# ShiftMux.net
KiCad netlist of a schematic drawn in Altium Designer
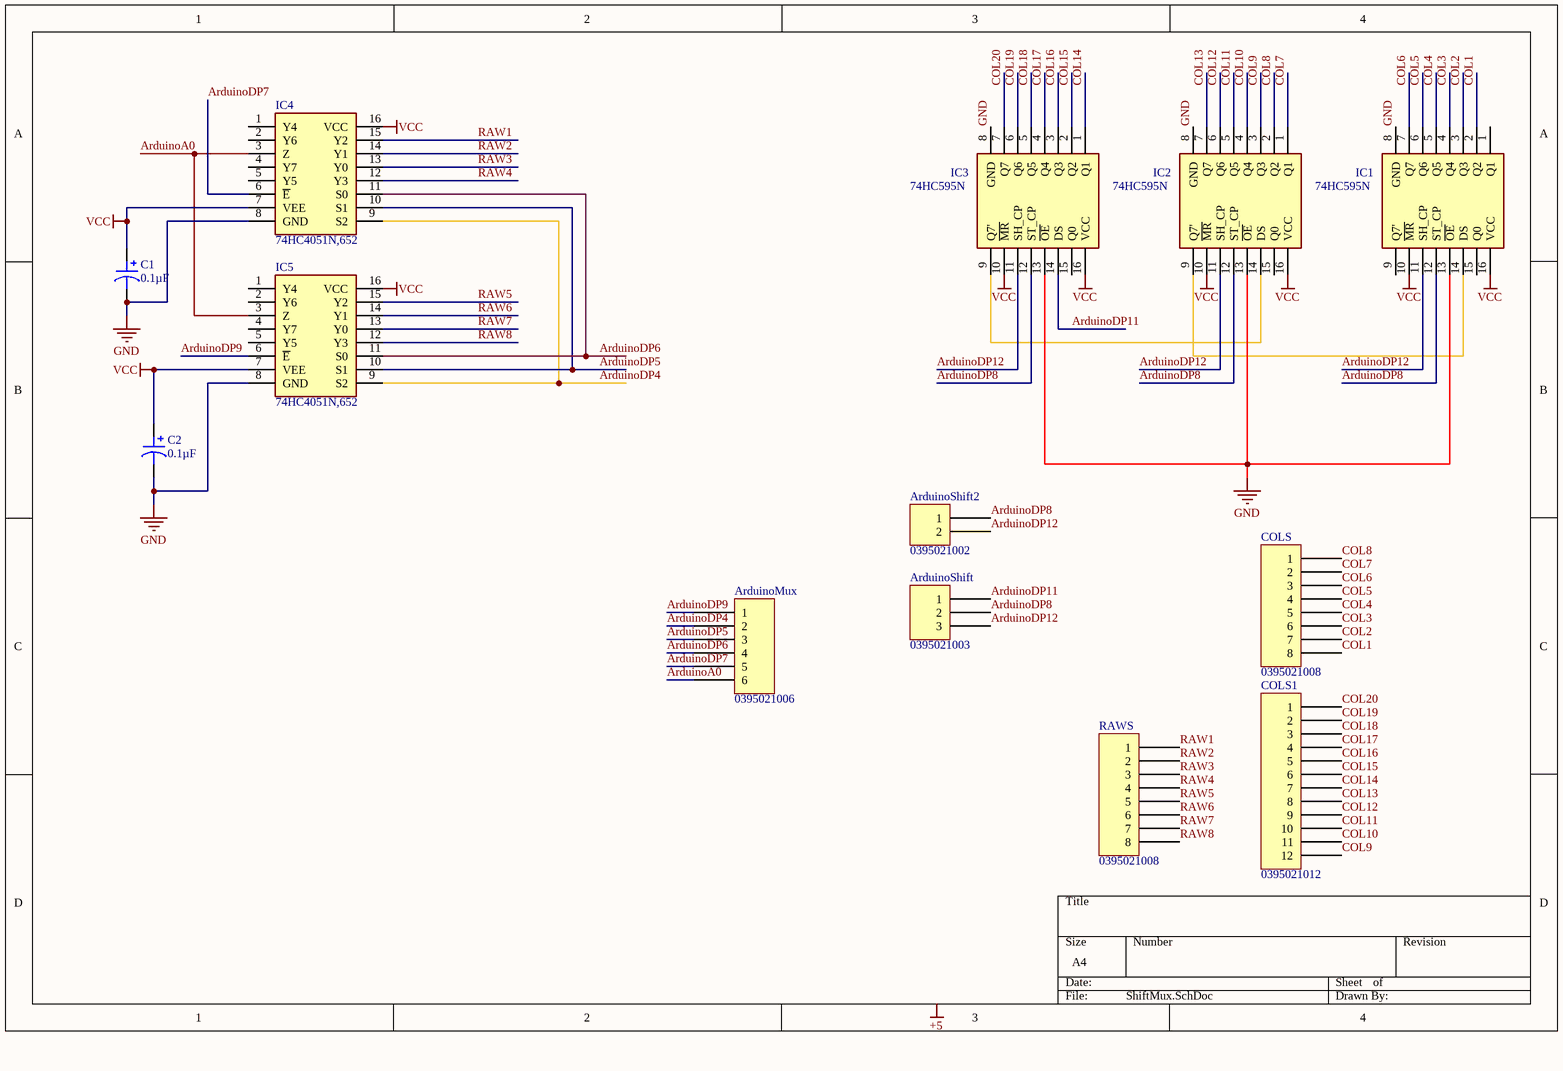
[diagram p0: ShiftMux.SchDoc]

(export (version "E")
  (design (tool "Eeschema 10.0.6"))
  (components
    (comp (ref "ArduinoMux")
      (value "0395021006")
      (footprint "MOLEX 395021006")
      (description "TERM BLOCK HDR 6POS 90DEG 3.5MM")
      (fields (field (name "MANUFACTURER") "Molex"))
      (libsource (lib "Celestial Altium Library - altium_library") (part "6 Pin"))
    )
    (comp (ref "ArduinoShift")
      (value "0395021003")
      (footprint "MOLEX 395021003")
      (description "TERM BLOCK HDR 3POS 90DEG 3.5MM")
      (fields (field (name "MANUFACTURER") "Molex"))
      (libsource (lib "Celestial Altium Library - altium_library") (part "3 Pin"))
    )
    (comp (ref "ArduinoShift2")
      (value "0395021002")
      (footprint "MOLEX 395021002")
      (description "TERM BLOCK HDR 2POS 90DEG 3.5MM")
      (fields (field (name "MANUFACTURER") "Molex"))
      (libsource (lib "Celestial Altium Library - altium_library") (part "2 Pin"))
    )
    (comp (ref "C1")
      (value "0.1µF")
      (footprint "CAP ALSMD POLY 4.3MM H5.5MM")
      (description "CAP ALUM 0.1UF 20% 63V SMD")
      (fields
        (field (name "PART NUMBER") "EMVA630ADAR10MD55G")
        (field (name "MANUFACTURER") "United Chemi-Con")
      )
      (libsource (lib "Celestial Altium Library - altium_library") (part "Polarised Capacitor"))
    )
    (comp (ref "C2")
      (value "0.1µF")
      (footprint "CAP ALSMD POLY 4.3MM H5.5MM")
      (description "CAP ALUM 0.1UF 20% 63V SMD")
      (fields
        (field (name "PART NUMBER") "EMVA630ADAR10MD55G")
        (field (name "MANUFACTURER") "United Chemi-Con")
      )
      (libsource (lib "Celestial Altium Library - altium_library") (part "Polarised Capacitor"))
    )
    (comp (ref "COLS")
      (value "0395021008")
      (footprint "MOLEX 395021008")
      (description "TERM BLOCK HDR 8POS 90DEG 3.5MM")
      (fields (field (name "MANUFACTURER") "Molex"))
      (libsource (lib "Celestial Altium Library - altium_library") (part "8 Pin"))
    )
    (comp (ref "COLS1")
      (value "0395021012")
      (footprint "MOLEX 395021012")
      (description "TERM BLOCK HDR 12POS 90DEG 3.5MM")
      (fields (field (name "MANUFACTURER") "Molex"))
      (libsource (lib "Celestial Altium Library - altium_library") (part "12 Pin"))
    )
    (comp (ref "IC1")
      (value "74HC595N")
      (footprint "SamacSys:DIP762W53P254L1902H420Q16N")
      (description "Integrated Circuit")
      (libsource (lib "*") (part "74HC595N"))
    )
    (comp (ref "IC2")
      (value "74HC595N")
      (footprint "SamacSys:DIP762W53P254L1902H420Q16N")
      (description "Integrated Circuit")
      (libsource (lib "*") (part "74HC595N"))
    )
    (comp (ref "IC3")
      (value "74HC595N")
      (footprint "SamacSys:DIP762W53P254L1902H420Q16N")
      (description "Integrated Circuit")
      (libsource (lib "*") (part "74HC595N"))
    )
    (comp (ref "IC4")
      (value "74HC4051N,652")
      (footprint "SamacSys:DIP802W53P254L1902H420Q16N")
      (description "Integrated Circuit")
      (libsource (lib "*") (part "74HC4051N,652"))
    )
    (comp (ref "IC5")
      (value "74HC4051N,652")
      (footprint "SamacSys:DIP802W53P254L1902H420Q16N")
      (description "Integrated Circuit")
      (libsource (lib "*") (part "74HC4051N,652"))
    )
    (comp (ref "RAWS")
      (value "0395021008")
      (footprint "MOLEX 395021008")
      (description "TERM BLOCK HDR 8POS 90DEG 3.5MM")
      (fields (field (name "MANUFACTURER") "Molex"))
      (libsource (lib "Celestial Altium Library - altium_library") (part "8 Pin"))
    )
  )
  (nets
    (net (code "2") (name "/ArduinoA0") (class "Default")
      (node (ref "ArduinoMux") (pin "6") (pinfunction "6_6") (pintype "passive"))
      (node (ref "IC4") (pin "3") (pinfunction "Z_3") (pintype "passive"))
      (node (ref "IC5") (pin "3") (pinfunction "Z_3") (pintype "passive"))
    )
    (net (code "3") (name "/ArduinoDP4") (class "Default")
      (node (ref "ArduinoMux") (pin "2") (pinfunction "2_2") (pintype "passive"))
      (node (ref "IC4") (pin "9") (pinfunction "S2_9") (pintype "passive"))
      (node (ref "IC5") (pin "9") (pinfunction "S2_9") (pintype "passive"))
    )
    (net (code "4") (name "/ArduinoDP5") (class "Default")
      (node (ref "ArduinoMux") (pin "3") (pinfunction "3_3") (pintype "passive"))
      (node (ref "IC4") (pin "10") (pinfunction "S1_10") (pintype "passive"))
      (node (ref "IC5") (pin "10") (pinfunction "S1_10") (pintype "passive"))
    )
    (net (code "5") (name "/ArduinoDP6") (class "Default")
      (node (ref "ArduinoMux") (pin "4") (pinfunction "4_4") (pintype "passive"))
      (node (ref "IC4") (pin "11") (pinfunction "S0_11") (pintype "passive"))
      (node (ref "IC5") (pin "11") (pinfunction "S0_11") (pintype "passive"))
    )
    (net (code "6") (name "/ArduinoDP7") (class "Default")
      (node (ref "ArduinoMux") (pin "5") (pinfunction "5_5") (pintype "passive"))
      (node (ref "IC4") (pin "6") (pinfunction "~{E}_6") (pintype "passive"))
    )
    (net (code "7") (name "/ArduinoDP8") (class "Default")
      (node (ref "ArduinoShift") (pin "2") (pinfunction "2_2") (pintype "passive"))
      (node (ref "ArduinoShift2") (pin "1") (pinfunction "1_1") (pintype "passive"))
      (node (ref "IC1") (pin "12") (pinfunction "ST_CP_12") (pintype "passive"))
      (node (ref "IC2") (pin "12") (pinfunction "ST_CP_12") (pintype "passive"))
      (node (ref "IC3") (pin "12") (pinfunction "ST_CP_12") (pintype "passive"))
    )
    (net (code "8") (name "/ArduinoDP9") (class "Default")
      (node (ref "ArduinoMux") (pin "1") (pinfunction "1_1") (pintype "passive"))
      (node (ref "IC5") (pin "6") (pinfunction "~{E}_6") (pintype "passive"))
    )
    (net (code "9") (name "/ArduinoDP11") (class "Default")
      (node (ref "ArduinoShift") (pin "1") (pinfunction "1_1") (pintype "passive"))
      (node (ref "IC3") (pin "14") (pinfunction "DS_14") (pintype "passive"))
    )
    (net (code "10") (name "/ArduinoDP12") (class "Default")
      (node (ref "ArduinoShift") (pin "3") (pinfunction "3_3") (pintype "passive"))
      (node (ref "ArduinoShift2") (pin "2") (pinfunction "2_2") (pintype "passive"))
      (node (ref "IC1") (pin "11") (pinfunction "SH_CP_11") (pintype "passive"))
      (node (ref "IC2") (pin "11") (pinfunction "SH_CP_11") (pintype "passive"))
      (node (ref "IC3") (pin "11") (pinfunction "SH_CP_11") (pintype "passive"))
    )
    (net (code "11") (name "/COL1") (class "Default")
      (node (ref "COLS") (pin "8") (pinfunction "8_8") (pintype "passive"))
      (node (ref "IC1") (pin "2") (pinfunction "Q2_2") (pintype "passive"))
    )
    (net (code "12") (name "/COL2") (class "Default")
      (node (ref "COLS") (pin "7") (pinfunction "7_7") (pintype "passive"))
      (node (ref "IC1") (pin "3") (pinfunction "Q3_3") (pintype "passive"))
    )
    (net (code "13") (name "/COL3") (class "Default")
      (node (ref "COLS") (pin "6") (pinfunction "6_6") (pintype "passive"))
      (node (ref "IC1") (pin "4") (pinfunction "Q4_4") (pintype "passive"))
    )
    (net (code "14") (name "/COL4") (class "Default")
      (node (ref "COLS") (pin "5") (pinfunction "5_5") (pintype "passive"))
      (node (ref "IC1") (pin "5") (pinfunction "Q5_5") (pintype "passive"))
    )
    (net (code "15") (name "/COL5") (class "Default")
      (node (ref "COLS") (pin "4") (pinfunction "4_4") (pintype "passive"))
      (node (ref "IC1") (pin "6") (pinfunction "Q6_6") (pintype "passive"))
    )
    (net (code "16") (name "/COL6") (class "Default")
      (node (ref "COLS") (pin "3") (pinfunction "3_3") (pintype "passive"))
      (node (ref "IC1") (pin "7") (pinfunction "Q7_7") (pintype "passive"))
    )
    (net (code "17") (name "/COL7") (class "Default")
      (node (ref "COLS") (pin "2") (pinfunction "2_2") (pintype "passive"))
      (node (ref "IC2") (pin "1") (pinfunction "Q1_1") (pintype "passive"))
    )
    (net (code "18") (name "/COL8") (class "Default")
      (node (ref "COLS") (pin "1") (pinfunction "1_1") (pintype "passive"))
      (node (ref "IC2") (pin "2") (pinfunction "Q2_2") (pintype "passive"))
    )
    (net (code "19") (name "/COL9") (class "Default")
      (node (ref "COLS1") (pin "12") (pinfunction "12_12") (pintype "passive"))
      (node (ref "IC2") (pin "3") (pinfunction "Q3_3") (pintype "passive"))
    )
    (net (code "20") (name "/COL10") (class "Default")
      (node (ref "COLS1") (pin "11") (pinfunction "11_11") (pintype "passive"))
      (node (ref "IC2") (pin "4") (pinfunction "Q4_4") (pintype "passive"))
    )
    (net (code "21") (name "/COL11") (class "Default")
      (node (ref "COLS1") (pin "10") (pinfunction "10_10") (pintype "passive"))
      (node (ref "IC2") (pin "5") (pinfunction "Q5_5") (pintype "passive"))
    )
    (net (code "22") (name "/COL12") (class "Default")
      (node (ref "COLS1") (pin "9") (pinfunction "9_9") (pintype "passive"))
      (node (ref "IC2") (pin "6") (pinfunction "Q6_6") (pintype "passive"))
    )
    (net (code "23") (name "/COL13") (class "Default")
      (node (ref "COLS1") (pin "8") (pinfunction "8_8") (pintype "passive"))
      (node (ref "IC2") (pin "7") (pinfunction "Q7_7") (pintype "passive"))
    )
    (net (code "24") (name "/COL14") (class "Default")
      (node (ref "COLS1") (pin "7") (pinfunction "7_7") (pintype "passive"))
      (node (ref "IC3") (pin "1") (pinfunction "Q1_1") (pintype "passive"))
    )
    (net (code "25") (name "/COL15") (class "Default")
      (node (ref "COLS1") (pin "6") (pinfunction "6_6") (pintype "passive"))
      (node (ref "IC3") (pin "2") (pinfunction "Q2_2") (pintype "passive"))
    )
    (net (code "26") (name "/COL16") (class "Default")
      (node (ref "COLS1") (pin "5") (pinfunction "5_5") (pintype "passive"))
      (node (ref "IC3") (pin "3") (pinfunction "Q3_3") (pintype "passive"))
    )
    (net (code "27") (name "/COL17") (class "Default")
      (node (ref "COLS1") (pin "4") (pinfunction "4_4") (pintype "passive"))
      (node (ref "IC3") (pin "4") (pinfunction "Q4_4") (pintype "passive"))
    )
    (net (code "28") (name "/COL18") (class "Default")
      (node (ref "COLS1") (pin "3") (pinfunction "3_3") (pintype "passive"))
      (node (ref "IC3") (pin "5") (pinfunction "Q5_5") (pintype "passive"))
    )
    (net (code "29") (name "/COL19") (class "Default")
      (node (ref "COLS1") (pin "2") (pinfunction "2_2") (pintype "passive"))
      (node (ref "IC3") (pin "6") (pinfunction "Q6_6") (pintype "passive"))
    )
    (net (code "30") (name "/COL20") (class "Default")
      (node (ref "COLS1") (pin "1") (pinfunction "1_1") (pintype "passive"))
      (node (ref "IC3") (pin "7") (pinfunction "Q7_7") (pintype "passive"))
    )
    (net (code "31") (name "/RAW1") (class "Default")
      (node (ref "IC4") (pin "15") (pinfunction "Y2_15") (pintype "passive"))
      (node (ref "RAWS") (pin "1") (pinfunction "1_1") (pintype "passive"))
    )
    (net (code "32") (name "/RAW2") (class "Default")
      (node (ref "IC4") (pin "14") (pinfunction "Y1_14") (pintype "passive"))
      (node (ref "RAWS") (pin "2") (pinfunction "2_2") (pintype "passive"))
    )
    (net (code "33") (name "/RAW3") (class "Default")
      (node (ref "IC4") (pin "13") (pinfunction "Y0_13") (pintype "passive"))
      (node (ref "RAWS") (pin "3") (pinfunction "3_3") (pintype "passive"))
    )
    (net (code "34") (name "/RAW4") (class "Default")
      (node (ref "IC4") (pin "12") (pinfunction "Y3_12") (pintype "passive"))
      (node (ref "RAWS") (pin "4") (pinfunction "4_4") (pintype "passive"))
    )
    (net (code "35") (name "/RAW5") (class "Default")
      (node (ref "IC5") (pin "15") (pinfunction "Y2_15") (pintype "passive"))
      (node (ref "RAWS") (pin "5") (pinfunction "5_5") (pintype "passive"))
    )
    (net (code "36") (name "/RAW6") (class "Default")
      (node (ref "IC5") (pin "14") (pinfunction "Y1_14") (pintype "passive"))
      (node (ref "RAWS") (pin "6") (pinfunction "6_6") (pintype "passive"))
    )
    (net (code "37") (name "/RAW7") (class "Default")
      (node (ref "IC5") (pin "13") (pinfunction "Y0_13") (pintype "passive"))
      (node (ref "RAWS") (pin "7") (pinfunction "7_7") (pintype "passive"))
    )
    (net (code "38") (name "/RAW8") (class "Default")
      (node (ref "IC5") (pin "12") (pinfunction "Y3_12") (pintype "passive"))
      (node (ref "RAWS") (pin "8") (pinfunction "8_8") (pintype "passive"))
    )
    (net (code "39") (name "GND") (class "Default")
      (node (ref "C1") (pin "2") (pinfunction "2_2") (pintype "passive"))
      (node (ref "C2") (pin "2") (pinfunction "2_2") (pintype "passive"))
      (node (ref "IC1") (pin "13") (pinfunction "~{OE}_13") (pintype "passive"))
      (node (ref "IC1") (pin "8") (pinfunction "GND_8") (pintype "passive"))
      (node (ref "IC2") (pin "13") (pinfunction "~{OE}_13") (pintype "passive"))
      (node (ref "IC2") (pin "8") (pinfunction "GND_8") (pintype "passive"))
      (node (ref "IC3") (pin "13") (pinfunction "~{OE}_13") (pintype "passive"))
      (node (ref "IC3") (pin "8") (pinfunction "GND_8") (pintype "passive"))
      (node (ref "IC4") (pin "8") (pinfunction "GND_8") (pintype "passive"))
      (node (ref "IC5") (pin "8") (pinfunction "GND_8") (pintype "passive"))
    )
    (net (code "40") (name "Net-(IC1-DS)") (class "Default")
      (node (ref "IC1") (pin "14") (pinfunction "DS_14") (pintype "passive"))
      (node (ref "IC2") (pin "9") (pinfunction "Q7'_9") (pintype "passive"))
    )
    (net (code "41") (name "Net-(IC2-DS)") (class "Default")
      (node (ref "IC2") (pin "14") (pinfunction "DS_14") (pintype "passive"))
      (node (ref "IC3") (pin "9") (pinfunction "Q7'_9") (pintype "passive"))
    )
    (net (code "42") (name "VCC") (class "Default")
      (node (ref "C1") (pin "1") (pinfunction "1_1") (pintype "passive"))
      (node (ref "C2") (pin "1") (pinfunction "1_1") (pintype "passive"))
      (node (ref "IC1") (pin "10") (pinfunction "~{MR}_10") (pintype "passive"))
      (node (ref "IC1") (pin "16") (pinfunction "VCC_16") (pintype "passive"))
      (node (ref "IC2") (pin "10") (pinfunction "~{MR}_10") (pintype "passive"))
      (node (ref "IC2") (pin "16") (pinfunction "VCC_16") (pintype "passive"))
      (node (ref "IC3") (pin "10") (pinfunction "~{MR}_10") (pintype "passive"))
      (node (ref "IC3") (pin "16") (pinfunction "VCC_16") (pintype "passive"))
      (node (ref "IC4") (pin "16") (pinfunction "VCC_16") (pintype "passive"))
      (node (ref "IC4") (pin "7") (pinfunction "VEE_7") (pintype "passive"))
      (node (ref "IC5") (pin "16") (pinfunction "VCC_16") (pintype "passive"))
      (node (ref "IC5") (pin "7") (pinfunction "VEE_7") (pintype "passive"))
    )
    (net (code "43") (name "unconnected-(IC1-Q0-Pad15)") (class "Default")
      (node (ref "IC1") (pin "15") (pinfunction "Q0_15") (pintype "passive"))
    )
    (net (code "44") (name "unconnected-(IC1-Q1-Pad1)") (class "Default")
      (node (ref "IC1") (pin "1") (pinfunction "Q1_1") (pintype "passive"))
    )
    (net (code "45") (name "unconnected-(IC1-Q7'-Pad9)") (class "Default")
      (node (ref "IC1") (pin "9") (pinfunction "Q7'_9") (pintype "passive"))
    )
    (net (code "46") (name "unconnected-(IC2-Q0-Pad15)") (class "Default")
      (node (ref "IC2") (pin "15") (pinfunction "Q0_15") (pintype "passive"))
    )
    (net (code "47") (name "unconnected-(IC3-Q0-Pad15)") (class "Default")
      (node (ref "IC3") (pin "15") (pinfunction "Q0_15") (pintype "passive"))
    )
    (net (code "48") (name "unconnected-(IC4-Y4-Pad1)") (class "Default")
      (node (ref "IC4") (pin "1") (pinfunction "Y4_1") (pintype "passive"))
    )
    (net (code "49") (name "unconnected-(IC4-Y5-Pad5)") (class "Default")
      (node (ref "IC4") (pin "5") (pinfunction "Y5_5") (pintype "passive"))
    )
    (net (code "50") (name "unconnected-(IC4-Y6-Pad2)") (class "Default")
      (node (ref "IC4") (pin "2") (pinfunction "Y6_2") (pintype "passive"))
    )
    (net (code "51") (name "unconnected-(IC4-Y7-Pad4)") (class "Default")
      (node (ref "IC4") (pin "4") (pinfunction "Y7_4") (pintype "passive"))
    )
    (net (code "52") (name "unconnected-(IC5-Y4-Pad1)") (class "Default")
      (node (ref "IC5") (pin "1") (pinfunction "Y4_1") (pintype "passive"))
    )
    (net (code "53") (name "unconnected-(IC5-Y5-Pad5)") (class "Default")
      (node (ref "IC5") (pin "5") (pinfunction "Y5_5") (pintype "passive"))
    )
    (net (code "54") (name "unconnected-(IC5-Y6-Pad2)") (class "Default")
      (node (ref "IC5") (pin "2") (pinfunction "Y6_2") (pintype "passive"))
    )
    (net (code "55") (name "unconnected-(IC5-Y7-Pad4)") (class "Default")
      (node (ref "IC5") (pin "4") (pinfunction "Y7_4") (pintype "passive"))
    )
  )
)
